# StepperInterface.net
KiCad netlist of a schematic drawn in Altium Designer
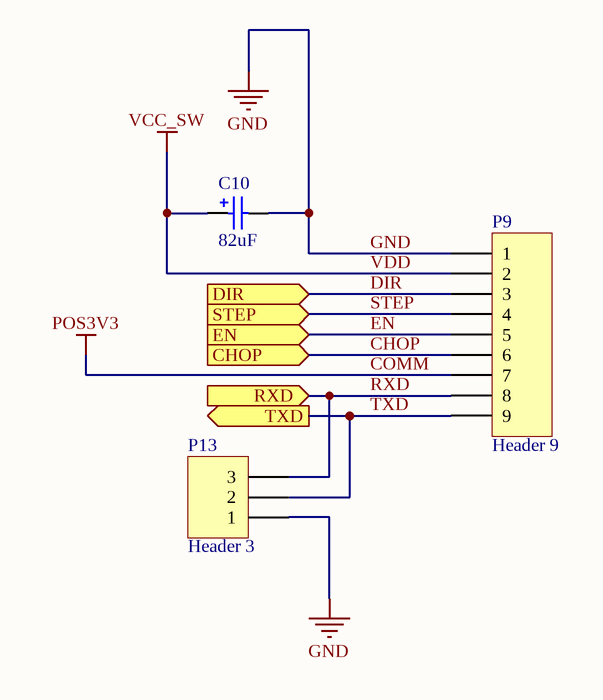
[diagram p0: StepperInterface.SchDoc]

(export (version "E")
  (design (tool "Eeschema 10.0.6"))
  (components
    (comp (ref "C10")
      (value "82uF")
      (footprint "CAP_EEFK_D8")
      (description "Polarized Capacitor (Surface Mount)")
      (fields (field (name "MANUFACTURER_PART_NUMBER") "EEEFK1V680XP"))
      (libsource (lib "AEVC-lib") (part "EEEFK1V680XP"))
    )
    (comp (ref "P9")
      (value "Header 9")
      (footprint "HDR1X9")
      (description "Header, 9-Pin")
      (fields (field (name "PUBLISHER") "Altium Limited"))
      (libsource (lib "Miscellaneous Connectors") (part "Header 9"))
    )
    (comp (ref "P13")
      (value "Header 3")
      (footprint "HDR1X3")
      (description "Header, 3-Pin")
      (fields (field (name "PUBLISHER") "Altium Limited"))
      (libsource (lib "Miscellaneous Connectors") (part "Header 3"))
    )
  )
  (nets
    (net (code "1") (name "/CHOP") (class "Default")
      (node (ref "P9") (pin "6") (pinfunction "6_6") (pintype "passive"))
    )
    (net (code "2") (name "/DIR") (class "Default")
      (node (ref "P9") (pin "3") (pinfunction "3_3") (pintype "passive"))
    )
    (net (code "3") (name "/EN") (class "Default")
      (node (ref "P9") (pin "5") (pinfunction "5_5") (pintype "passive"))
    )
    (net (code "4") (name "/RXD") (class "Default")
      (node (ref "P13") (pin "3") (pinfunction "3_3") (pintype "passive"))
      (node (ref "P9") (pin "8") (pinfunction "8_8") (pintype "passive"))
    )
    (net (code "5") (name "/STEP") (class "Default")
      (node (ref "P9") (pin "4") (pinfunction "4_4") (pintype "passive"))
    )
    (net (code "6") (name "/TXD") (class "Default")
      (node (ref "P13") (pin "2") (pinfunction "2_2") (pintype "passive"))
      (node (ref "P9") (pin "9") (pinfunction "9_9") (pintype "passive"))
    )
    (net (code "7") (name "GND") (class "Default")
      (node (ref "C10") (pin "2") (pinfunction "2_2") (pintype "passive"))
      (node (ref "P13") (pin "1") (pinfunction "1_1") (pintype "passive"))
      (node (ref "P9") (pin "1") (pinfunction "1_1") (pintype "passive"))
    )
    (net (code "8") (name "POS3V3") (class "Default")
      (node (ref "P9") (pin "7") (pinfunction "7_7") (pintype "passive"))
    )
    (net (code "9") (name "VCC_SW") (class "Default")
      (node (ref "C10") (pin "1") (pinfunction "1_1") (pintype "passive"))
      (node (ref "P9") (pin "2") (pinfunction "2_2") (pintype "passive"))
    )
  )
)
